# awc_v2.net
KiCad netlist of a schematic drawn in EAGLE
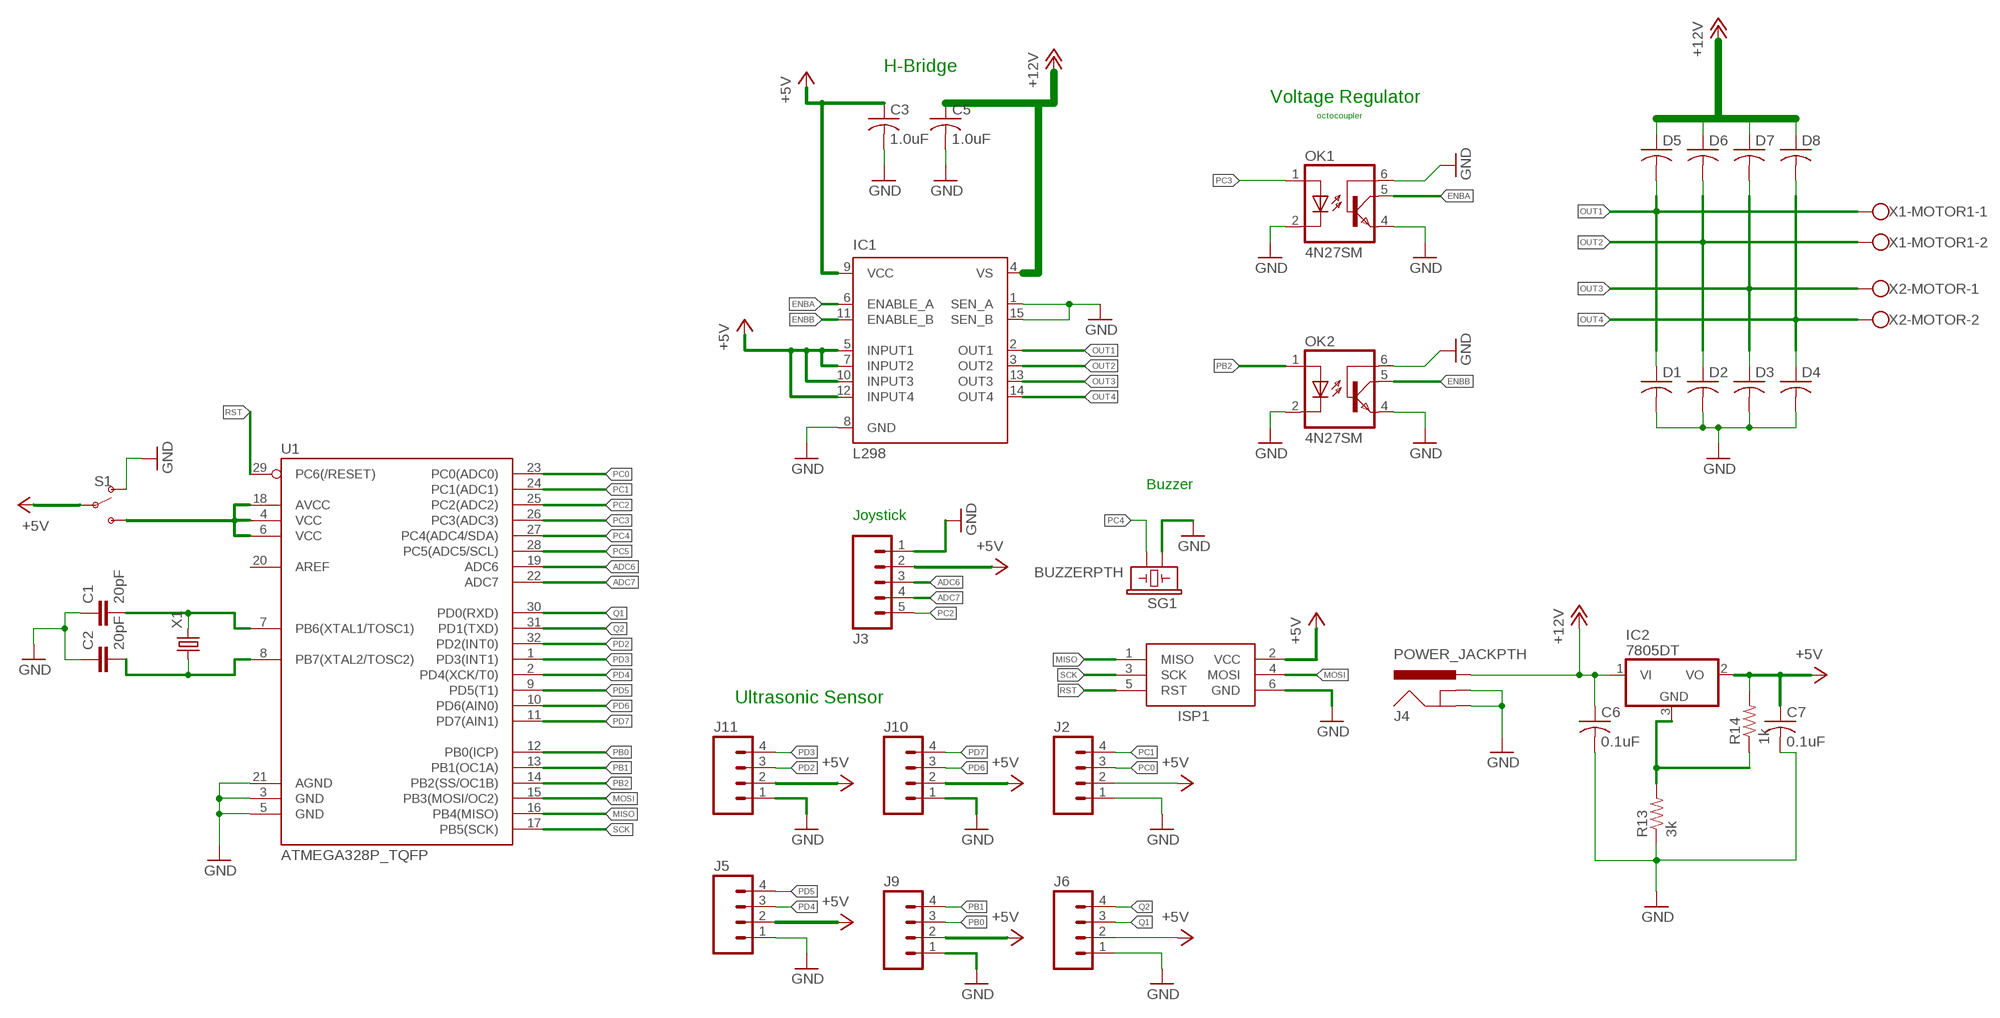
[diagram p0: schematic, sheet 1]

(export (version "E")
  (design (tool "Eeschema 10.0.6"))
  (components
    (comp (ref "C1")
      (value "20pF")
      (footprint "eagle-import:C0805")
      (libsource (lib "eagle-import") (part "C-EUC0805"))
    )
    (comp (ref "C2")
      (value "20pF")
      (footprint "eagle-import:C0805")
      (libsource (lib "eagle-import") (part "C-EUC0805"))
    )
    (comp (ref "C3")
      (value "1.0uF")
      (footprint "eagle-import:C0805")
      (libsource (lib "eagle-import") (part "C-USC0805"))
    )
    (comp (ref "C5")
      (value "1.0uF")
      (footprint "eagle-import:C0805")
      (libsource (lib "eagle-import") (part "C-USC0805"))
    )
    (comp (ref "C6")
      (value "0.1uF")
      (footprint "eagle-import:C0805")
      (libsource (lib "eagle-import") (part "C-USC0805"))
    )
    (comp (ref "C7")
      (value "0.1uF")
      (footprint "eagle-import:C0805")
      (libsource (lib "eagle-import") (part "C-USC0805"))
    )
    (comp (ref "D1")
      (value "C-USC0805")
      (footprint "eagle-import:C0805")
      (libsource (lib "eagle-import") (part "C-USC0805"))
    )
    (comp (ref "D2")
      (value "C-USC0805")
      (footprint "eagle-import:C0805")
      (libsource (lib "eagle-import") (part "C-USC0805"))
    )
    (comp (ref "D3")
      (value "C-USC0805")
      (footprint "eagle-import:C0805")
      (libsource (lib "eagle-import") (part "C-USC0805"))
    )
    (comp (ref "D4")
      (value "C-USC0805")
      (footprint "eagle-import:C0805")
      (libsource (lib "eagle-import") (part "C-USC0805"))
    )
    (comp (ref "D5")
      (value "C-USC0805")
      (footprint "eagle-import:C0805")
      (libsource (lib "eagle-import") (part "C-USC0805"))
    )
    (comp (ref "D6")
      (value "C-USC0805")
      (footprint "eagle-import:C0805")
      (libsource (lib "eagle-import") (part "C-USC0805"))
    )
    (comp (ref "D7")
      (value "C-USC0805")
      (footprint "eagle-import:C0805")
      (libsource (lib "eagle-import") (part "C-USC0805"))
    )
    (comp (ref "D8")
      (value "C-USC0805")
      (footprint "eagle-import:C0805")
      (libsource (lib "eagle-import") (part "C-USC0805"))
    )
    (comp (ref "IC1")
      (value "L298")
      (footprint "eagle-import:MULTIWATT-15")
      (fields (field (name "MPN") "L298N"))
      (libsource (lib "eagle-import") (part "L298"))
    )
    (comp (ref "IC2")
      (value "7805DT")
      (footprint "eagle-import:TO252")
      (libsource (lib "eagle-import") (part "78DT05"))
    )
    (comp (ref "ISP1")
      (value "AVRISP-6")
      (footprint "eagle-import:AVRISP")
      (libsource (lib "eagle-import") (part "AVRISP-6"))
    )
    (comp (ref "J2")
      (value "M04SCREW_LOCK")
      (footprint "eagle-import:SCREWTERMINAL-3.5MM-4_LOCK")
      (libsource (lib "eagle-import") (part "M04SCREW_LOCK"))
    )
    (comp (ref "J3")
      (value "M05SCREW")
      (footprint "eagle-import:SCREWTERMINAL-3.5MM-5")
      (libsource (lib "eagle-import") (part "M05SCREW"))
    )
    (comp (ref "J4")
      (value "POWER_JACKPTH")
      (footprint "eagle-import:POWER_JACK_PTH")
      (libsource (lib "eagle-import") (part "POWER_JACKPTH"))
    )
    (comp (ref "J5")
      (value "M04SCREW_LOCK")
      (footprint "eagle-import:SCREWTERMINAL-3.5MM-4_LOCK")
      (libsource (lib "eagle-import") (part "M04SCREW_LOCK"))
    )
    (comp (ref "J6")
      (value "M04SCREW_LOCK")
      (footprint "eagle-import:SCREWTERMINAL-3.5MM-4_LOCK")
      (libsource (lib "eagle-import") (part "M04SCREW_LOCK"))
    )
    (comp (ref "J9")
      (value "M04SCREW_LOCK")
      (footprint "eagle-import:SCREWTERMINAL-3.5MM-4_LOCK")
      (libsource (lib "eagle-import") (part "M04SCREW_LOCK"))
    )
    (comp (ref "J10")
      (value "M04SCREW_LOCK")
      (footprint "eagle-import:SCREWTERMINAL-3.5MM-4_LOCK")
      (libsource (lib "eagle-import") (part "M04SCREW_LOCK"))
    )
    (comp (ref "J11")
      (value "M04SCREW_LOCK")
      (footprint "eagle-import:SCREWTERMINAL-3.5MM-4_LOCK")
      (libsource (lib "eagle-import") (part "M04SCREW_LOCK"))
    )
    (comp (ref "OK1")
      (value "4N27SM")
      (footprint "eagle-import:DIL6-SMD")
      (fields (field (name "MF") "FAIRCHILD SEMICONDUCTOR") (field (name "MPN") "4N27S-M"))
      (libsource (lib "eagle-import") (part "4N?MS27"))
    )
    (comp (ref "OK2")
      (value "4N27SM")
      (footprint "eagle-import:DIL6-SMD")
      (fields (field (name "MF") "FAIRCHILD SEMICONDUCTOR") (field (name "MPN") "4N27S-M"))
      (libsource (lib "eagle-import") (part "4N?MS27"))
    )
    (comp (ref "R13")
      (value "3k")
      (footprint "eagle-import:0402-RES")
      (libsource (lib "eagle-import") (part "RESISTOR0402"))
    )
    (comp (ref "R14")
      (value "1k")
      (footprint "eagle-import:M0805")
      (libsource (lib "eagle-import") (part "R-US_M0805"))
    )
    (comp (ref "S1")
      (value "SWITCH-SPDT-PTH-11.6X4.0MM")
      (footprint "eagle-import:SWITCH_SPDT_PTH_11.6X4.0MM")
      (libsource (lib "eagle-import") (part "SWITCH-SPDT-PTH-11.6X4.0MM"))
    )
    (comp (ref "SG1")
      (value "BUZZERPTH")
      (footprint "eagle-import:BUZZER-12MM")
      (libsource (lib "eagle-import") (part "BUZZERPTH"))
    )
    (comp (ref "U1")
      (value "ATMEGA328P_TQFP")
      (footprint "eagle-import:TQFP32-08")
      (libsource (lib "eagle-import") (part "ATMEGA328P_TQFP"))
    )
    (comp (ref "X1")
      (value "CRYSTALHC49UP")
      (footprint "eagle-import:HC49UP")
      (libsource (lib "eagle-import") (part "CRYSTALHC49UP"))
    )
    (comp (ref "X1-MOTOR1")
      (value "W237-102")
      (footprint "eagle-import:W237-102")
      (fields (field (name "MPN") "237-102"))
      (libsource (lib "eagle-import") (part "W237-102"))
    )
    (comp (ref "X2-MOTOR")
      (value "W237-102")
      (footprint "eagle-import:W237-102")
      (fields (field (name "MPN") "237-102"))
      (libsource (lib "eagle-import") (part "W237-102"))
    )
  )
  (nets
    (net (code "1") (name "+5V") (class "Default")
      (node (ref "C3") (pin "1") (pinfunction "1_1") (pintype "passive"))
      (node (ref "C7") (pin "1") (pinfunction "1_1") (pintype "passive"))
      (node (ref "IC1") (pin "10") (pinfunction "INPUT3_10") (pintype "input"))
      (node (ref "IC1") (pin "12") (pinfunction "INPUT4_12") (pintype "input"))
      (node (ref "IC1") (pin "5") (pinfunction "INPUT1_5") (pintype "input"))
      (node (ref "IC1") (pin "7") (pinfunction "INPUT2_7") (pintype "input"))
      (node (ref "IC1") (pin "9") (pinfunction "VCC_9") (pintype "power_in"))
      (node (ref "IC2") (pin "2") (pinfunction "VO_2") (pintype "passive"))
      (node (ref "ISP1") (pin "2") (pinfunction "VCC_2") (pintype "power_in"))
      (node (ref "J10") (pin "2") (pinfunction "2_2") (pintype "passive"))
      (node (ref "J11") (pin "2") (pinfunction "2_2") (pintype "passive"))
      (node (ref "J2") (pin "2") (pinfunction "2_2") (pintype "passive"))
      (node (ref "J3") (pin "2") (pinfunction "2_2") (pintype "passive"))
      (node (ref "J5") (pin "2") (pinfunction "2_2") (pintype "passive"))
      (node (ref "J6") (pin "2") (pinfunction "2_2") (pintype "passive"))
      (node (ref "J9") (pin "2") (pinfunction "2_2") (pintype "passive"))
      (node (ref "R14") (pin "2") (pinfunction "2_2") (pintype "passive"))
      (node (ref "S1") (pin "2") (pinfunction "P_2") (pintype "passive"))
    )
    (net (code "2") (name "+12V") (class "Default")
      (node (ref "C5") (pin "1") (pinfunction "1_1") (pintype "passive"))
      (node (ref "C6") (pin "1") (pinfunction "1_1") (pintype "passive"))
      (node (ref "D5") (pin "1") (pinfunction "1_1") (pintype "passive"))
      (node (ref "D6") (pin "1") (pinfunction "1_1") (pintype "passive"))
      (node (ref "D7") (pin "1") (pinfunction "1_1") (pintype "passive"))
      (node (ref "D8") (pin "1") (pinfunction "1_1") (pintype "passive"))
      (node (ref "IC1") (pin "4") (pinfunction "VS_4") (pintype "power_in"))
      (node (ref "IC2") (pin "1") (pinfunction "VI_1") (pintype "input"))
      (node (ref "J4") (pin "PWR") (pinfunction "PWR_PWR") (pintype "bidirectional"))
    )
    (net (code "3") (name "ADC6") (class "Default")
      (node (ref "J3") (pin "3") (pinfunction "3_3") (pintype "passive"))
      (node (ref "U1") (pin "19") (pinfunction "ADC6_19") (pintype "bidirectional"))
    )
    (net (code "4") (name "ADC7") (class "Default")
      (node (ref "J3") (pin "4") (pinfunction "4_4") (pintype "passive"))
      (node (ref "U1") (pin "22") (pinfunction "ADC7_22") (pintype "bidirectional"))
    )
    (net (code "5") (name "ENBA") (class "Default")
      (node (ref "IC1") (pin "6") (pinfunction "ENABLE_A_6") (pintype "input"))
      (node (ref "OK1") (pin "5") (pinfunction "COL_5") (pintype "passive"))
    )
    (net (code "6") (name "ENBB") (class "Default")
      (node (ref "IC1") (pin "11") (pinfunction "ENABLE_B_11") (pintype "input"))
      (node (ref "OK2") (pin "5") (pinfunction "COL_5") (pintype "passive"))
    )
    (net (code "7") (name "GND") (class "Default")
      (node (ref "C1") (pin "1") (pinfunction "1_1") (pintype "passive"))
      (node (ref "C2") (pin "1") (pinfunction "1_1") (pintype "passive"))
      (node (ref "C3") (pin "2") (pinfunction "2_2") (pintype "passive"))
      (node (ref "C5") (pin "2") (pinfunction "2_2") (pintype "passive"))
      (node (ref "C6") (pin "2") (pinfunction "2_2") (pintype "passive"))
      (node (ref "C7") (pin "2") (pinfunction "2_2") (pintype "passive"))
      (node (ref "D1") (pin "2") (pinfunction "2_2") (pintype "passive"))
      (node (ref "D2") (pin "2") (pinfunction "2_2") (pintype "passive"))
      (node (ref "D3") (pin "2") (pinfunction "2_2") (pintype "passive"))
      (node (ref "D4") (pin "2") (pinfunction "2_2") (pintype "passive"))
      (node (ref "IC1") (pin "1") (pinfunction "SEN_A_1") (pintype "input"))
      (node (ref "IC1") (pin "15") (pinfunction "SEN_B_15") (pintype "input"))
      (node (ref "IC1") (pin "8") (pinfunction "GND_8") (pintype "power_in"))
      (node (ref "ISP1") (pin "6") (pinfunction "GND_6") (pintype "power_in"))
      (node (ref "J10") (pin "1") (pinfunction "1_1") (pintype "passive"))
      (node (ref "J11") (pin "1") (pinfunction "1_1") (pintype "passive"))
      (node (ref "J2") (pin "1") (pinfunction "1_1") (pintype "passive"))
      (node (ref "J3") (pin "1") (pinfunction "1_1") (pintype "passive"))
      (node (ref "J4") (pin "GND") (pinfunction "GND_GND") (pintype "bidirectional"))
      (node (ref "J4") (pin "GNDBREAK") (pinfunction "GNDBREAK_GNDBREAK") (pintype "bidirectional"))
      (node (ref "J5") (pin "1") (pinfunction "1_1") (pintype "passive"))
      (node (ref "J6") (pin "1") (pinfunction "1_1") (pintype "passive"))
      (node (ref "J9") (pin "1") (pinfunction "1_1") (pintype "passive"))
      (node (ref "OK1") (pin "2") (pinfunction "C_2") (pintype "passive"))
      (node (ref "OK1") (pin "4") (pinfunction "EMI_4") (pintype "passive"))
      (node (ref "OK1") (pin "6") (pinfunction "BAS_6") (pintype "passive"))
      (node (ref "OK2") (pin "2") (pinfunction "C_2") (pintype "passive"))
      (node (ref "OK2") (pin "4") (pinfunction "EMI_4") (pintype "passive"))
      (node (ref "OK2") (pin "6") (pinfunction "BAS_6") (pintype "passive"))
      (node (ref "R13") (pin "1") (pinfunction "1_1") (pintype "passive"))
      (node (ref "S1") (pin "1") (pinfunction "O_1") (pintype "passive"))
      (node (ref "SG1") (pin "+") (pinfunction "1_+") (pintype "passive"))
      (node (ref "U1") (pin "21") (pinfunction "AGND_21") (pintype "bidirectional"))
      (node (ref "U1") (pin "3") (pinfunction "GND_3") (pintype "bidirectional"))
      (node (ref "U1") (pin "5") (pinfunction "GND_5") (pintype "bidirectional"))
    )
    (net (code "8") (name "MISO") (class "Default")
      (node (ref "ISP1") (pin "1") (pinfunction "MISO_1") (pintype "input"))
      (node (ref "U1") (pin "16") (pinfunction "PB4(MISO)_16") (pintype "bidirectional"))
    )
    (net (code "9") (name "MOSI") (class "Default")
      (node (ref "ISP1") (pin "4") (pinfunction "MOSI_4") (pintype "output"))
      (node (ref "U1") (pin "15") (pinfunction "PB3(MOSI/OC2)_15") (pintype "bidirectional"))
    )
    (net (code "10") (name "Net-(IC2-GND)") (class "Default")
      (node (ref "IC2") (pin "3") (pinfunction "GND_3") (pintype "passive"))
      (node (ref "R13") (pin "2") (pinfunction "2_2") (pintype "passive"))
      (node (ref "R14") (pin "1") (pinfunction "1_1") (pintype "passive"))
    )
    (net (code "11") (name "Net-(S1-S)") (class "Default")
      (node (ref "S1") (pin "3") (pinfunction "S_3") (pintype "passive"))
      (node (ref "U1") (pin "18") (pinfunction "AVCC_18") (pintype "bidirectional"))
      (node (ref "U1") (pin "4") (pinfunction "VCC_4") (pintype "bidirectional"))
      (node (ref "U1") (pin "6") (pinfunction "VCC_6") (pintype "bidirectional"))
    )
    (net (code "12") (name "Net-(U1-PB6(XTAL1{slash}TOSC1))") (class "Default")
      (node (ref "C1") (pin "2") (pinfunction "2_2") (pintype "passive"))
      (node (ref "U1") (pin "7") (pinfunction "PB6(XTAL1/TOSC1)_7") (pintype "bidirectional"))
      (node (ref "X1") (pin "2") (pinfunction "2_2") (pintype "passive"))
    )
    (net (code "13") (name "Net-(U1-PB7(XTAL2{slash}TOSC2))") (class "Default")
      (node (ref "C2") (pin "2") (pinfunction "2_2") (pintype "passive"))
      (node (ref "U1") (pin "8") (pinfunction "PB7(XTAL2/TOSC2)_8") (pintype "bidirectional"))
      (node (ref "X1") (pin "1") (pinfunction "1_1") (pintype "passive"))
    )
    (net (code "14") (name "OUT1") (class "Default")
      (node (ref "D1") (pin "1") (pinfunction "1_1") (pintype "passive"))
      (node (ref "D5") (pin "2") (pinfunction "2_2") (pintype "passive"))
      (node (ref "IC1") (pin "2") (pinfunction "OUT1_2") (pintype "output"))
      (node (ref "X1-MOTOR1") (pin "1") (pinfunction "KL_1") (pintype "passive"))
    )
    (net (code "15") (name "OUT2") (class "Default")
      (node (ref "D2") (pin "1") (pinfunction "1_1") (pintype "passive"))
      (node (ref "D6") (pin "2") (pinfunction "2_2") (pintype "passive"))
      (node (ref "IC1") (pin "3") (pinfunction "OUT2_3") (pintype "output"))
      (node (ref "X1-MOTOR1") (pin "2") (pinfunction "KL_2") (pintype "passive"))
    )
    (net (code "16") (name "OUT3") (class "Default")
      (node (ref "D3") (pin "1") (pinfunction "1_1") (pintype "passive"))
      (node (ref "D7") (pin "2") (pinfunction "2_2") (pintype "passive"))
      (node (ref "IC1") (pin "13") (pinfunction "OUT3_13") (pintype "output"))
      (node (ref "X2-MOTOR") (pin "1") (pinfunction "KL_1") (pintype "passive"))
    )
    (net (code "17") (name "OUT4") (class "Default")
      (node (ref "D4") (pin "1") (pinfunction "1_1") (pintype "passive"))
      (node (ref "D8") (pin "2") (pinfunction "2_2") (pintype "passive"))
      (node (ref "IC1") (pin "14") (pinfunction "OUT4_14") (pintype "output"))
      (node (ref "X2-MOTOR") (pin "2") (pinfunction "KL_2") (pintype "passive"))
    )
    (net (code "18") (name "PB0") (class "Default")
      (node (ref "J9") (pin "3") (pinfunction "3_3") (pintype "passive"))
      (node (ref "U1") (pin "12") (pinfunction "PB0(ICP)_12") (pintype "bidirectional"))
    )
    (net (code "19") (name "PB1") (class "Default")
      (node (ref "J9") (pin "4") (pinfunction "4_4") (pintype "passive"))
      (node (ref "U1") (pin "13") (pinfunction "PB1(OC1A)_13") (pintype "bidirectional"))
    )
    (net (code "20") (name "PB2") (class "Default")
      (node (ref "OK2") (pin "1") (pinfunction "A_1") (pintype "passive"))
      (node (ref "U1") (pin "14") (pinfunction "PB2(SS/OC1B)_14") (pintype "bidirectional"))
    )
    (net (code "21") (name "PC0") (class "Default")
      (node (ref "J2") (pin "3") (pinfunction "3_3") (pintype "passive"))
      (node (ref "U1") (pin "23") (pinfunction "PC0(ADC0)_23") (pintype "bidirectional"))
    )
    (net (code "22") (name "PC1") (class "Default")
      (node (ref "J2") (pin "4") (pinfunction "4_4") (pintype "passive"))
      (node (ref "U1") (pin "24") (pinfunction "PC1(ADC1)_24") (pintype "bidirectional"))
    )
    (net (code "23") (name "PC2") (class "Default")
      (node (ref "J3") (pin "5") (pinfunction "5_5") (pintype "passive"))
      (node (ref "U1") (pin "25") (pinfunction "PC2(ADC2)_25") (pintype "bidirectional"))
    )
    (net (code "24") (name "PC3") (class "Default")
      (node (ref "OK1") (pin "1") (pinfunction "A_1") (pintype "passive"))
      (node (ref "U1") (pin "26") (pinfunction "PC3(ADC3)_26") (pintype "bidirectional"))
    )
    (net (code "25") (name "PC4") (class "Default")
      (node (ref "SG1") (pin "-") (pinfunction "2_-") (pintype "passive"))
      (node (ref "U1") (pin "27") (pinfunction "PC4(ADC4/SDA)_27") (pintype "bidirectional"))
    )
    (net (code "26") (name "PC5") (class "Default")
      (node (ref "U1") (pin "28") (pinfunction "PC5(ADC5/SCL)_28") (pintype "bidirectional"))
    )
    (net (code "27") (name "PD2") (class "Default")
      (node (ref "J11") (pin "3") (pinfunction "3_3") (pintype "passive"))
      (node (ref "U1") (pin "32") (pinfunction "PD2(INT0)_32") (pintype "bidirectional"))
    )
    (net (code "28") (name "PD3") (class "Default")
      (node (ref "J11") (pin "4") (pinfunction "4_4") (pintype "passive"))
      (node (ref "U1") (pin "1") (pinfunction "PD3(INT1)_1") (pintype "bidirectional"))
    )
    (net (code "29") (name "PD4") (class "Default")
      (node (ref "J5") (pin "3") (pinfunction "3_3") (pintype "passive"))
      (node (ref "U1") (pin "2") (pinfunction "PD4(XCK/T0)_2") (pintype "bidirectional"))
    )
    (net (code "30") (name "PD5") (class "Default")
      (node (ref "J5") (pin "4") (pinfunction "4_4") (pintype "passive"))
      (node (ref "U1") (pin "9") (pinfunction "PD5(T1)_9") (pintype "bidirectional"))
    )
    (net (code "31") (name "PD6") (class "Default")
      (node (ref "J10") (pin "3") (pinfunction "3_3") (pintype "passive"))
      (node (ref "U1") (pin "10") (pinfunction "PD6(AIN0)_10") (pintype "bidirectional"))
    )
    (net (code "32") (name "PD7") (class "Default")
      (node (ref "J10") (pin "4") (pinfunction "4_4") (pintype "passive"))
      (node (ref "U1") (pin "11") (pinfunction "PD7(AIN1)_11") (pintype "bidirectional"))
    )
    (net (code "33") (name "Q1") (class "Default")
      (node (ref "J6") (pin "3") (pinfunction "3_3") (pintype "passive"))
      (node (ref "U1") (pin "30") (pinfunction "PD0(RXD)_30") (pintype "bidirectional"))
    )
    (net (code "34") (name "Q2") (class "Default")
      (node (ref "J6") (pin "4") (pinfunction "4_4") (pintype "passive"))
      (node (ref "U1") (pin "31") (pinfunction "PD1(TXD)_31") (pintype "bidirectional"))
    )
    (net (code "35") (name "RST") (class "Default")
      (node (ref "ISP1") (pin "5") (pinfunction "RST_5") (pintype "output"))
      (node (ref "U1") (pin "29") (pinfunction "PC6(/RESET)_29") (pintype "bidirectional"))
    )
    (net (code "36") (name "SCK") (class "Default")
      (node (ref "ISP1") (pin "3") (pinfunction "SCK_3") (pintype "output"))
      (node (ref "U1") (pin "17") (pinfunction "PB5(SCK)_17") (pintype "bidirectional"))
    )
    (net (code "37") (name "unconnected-(U1-AREF-Pad20)") (class "Default")
      (node (ref "U1") (pin "20") (pinfunction "AREF_20") (pintype "bidirectional"))
    )
  )
)
